# shed.net
KiCad netlist of a schematic drawn in EAGLE
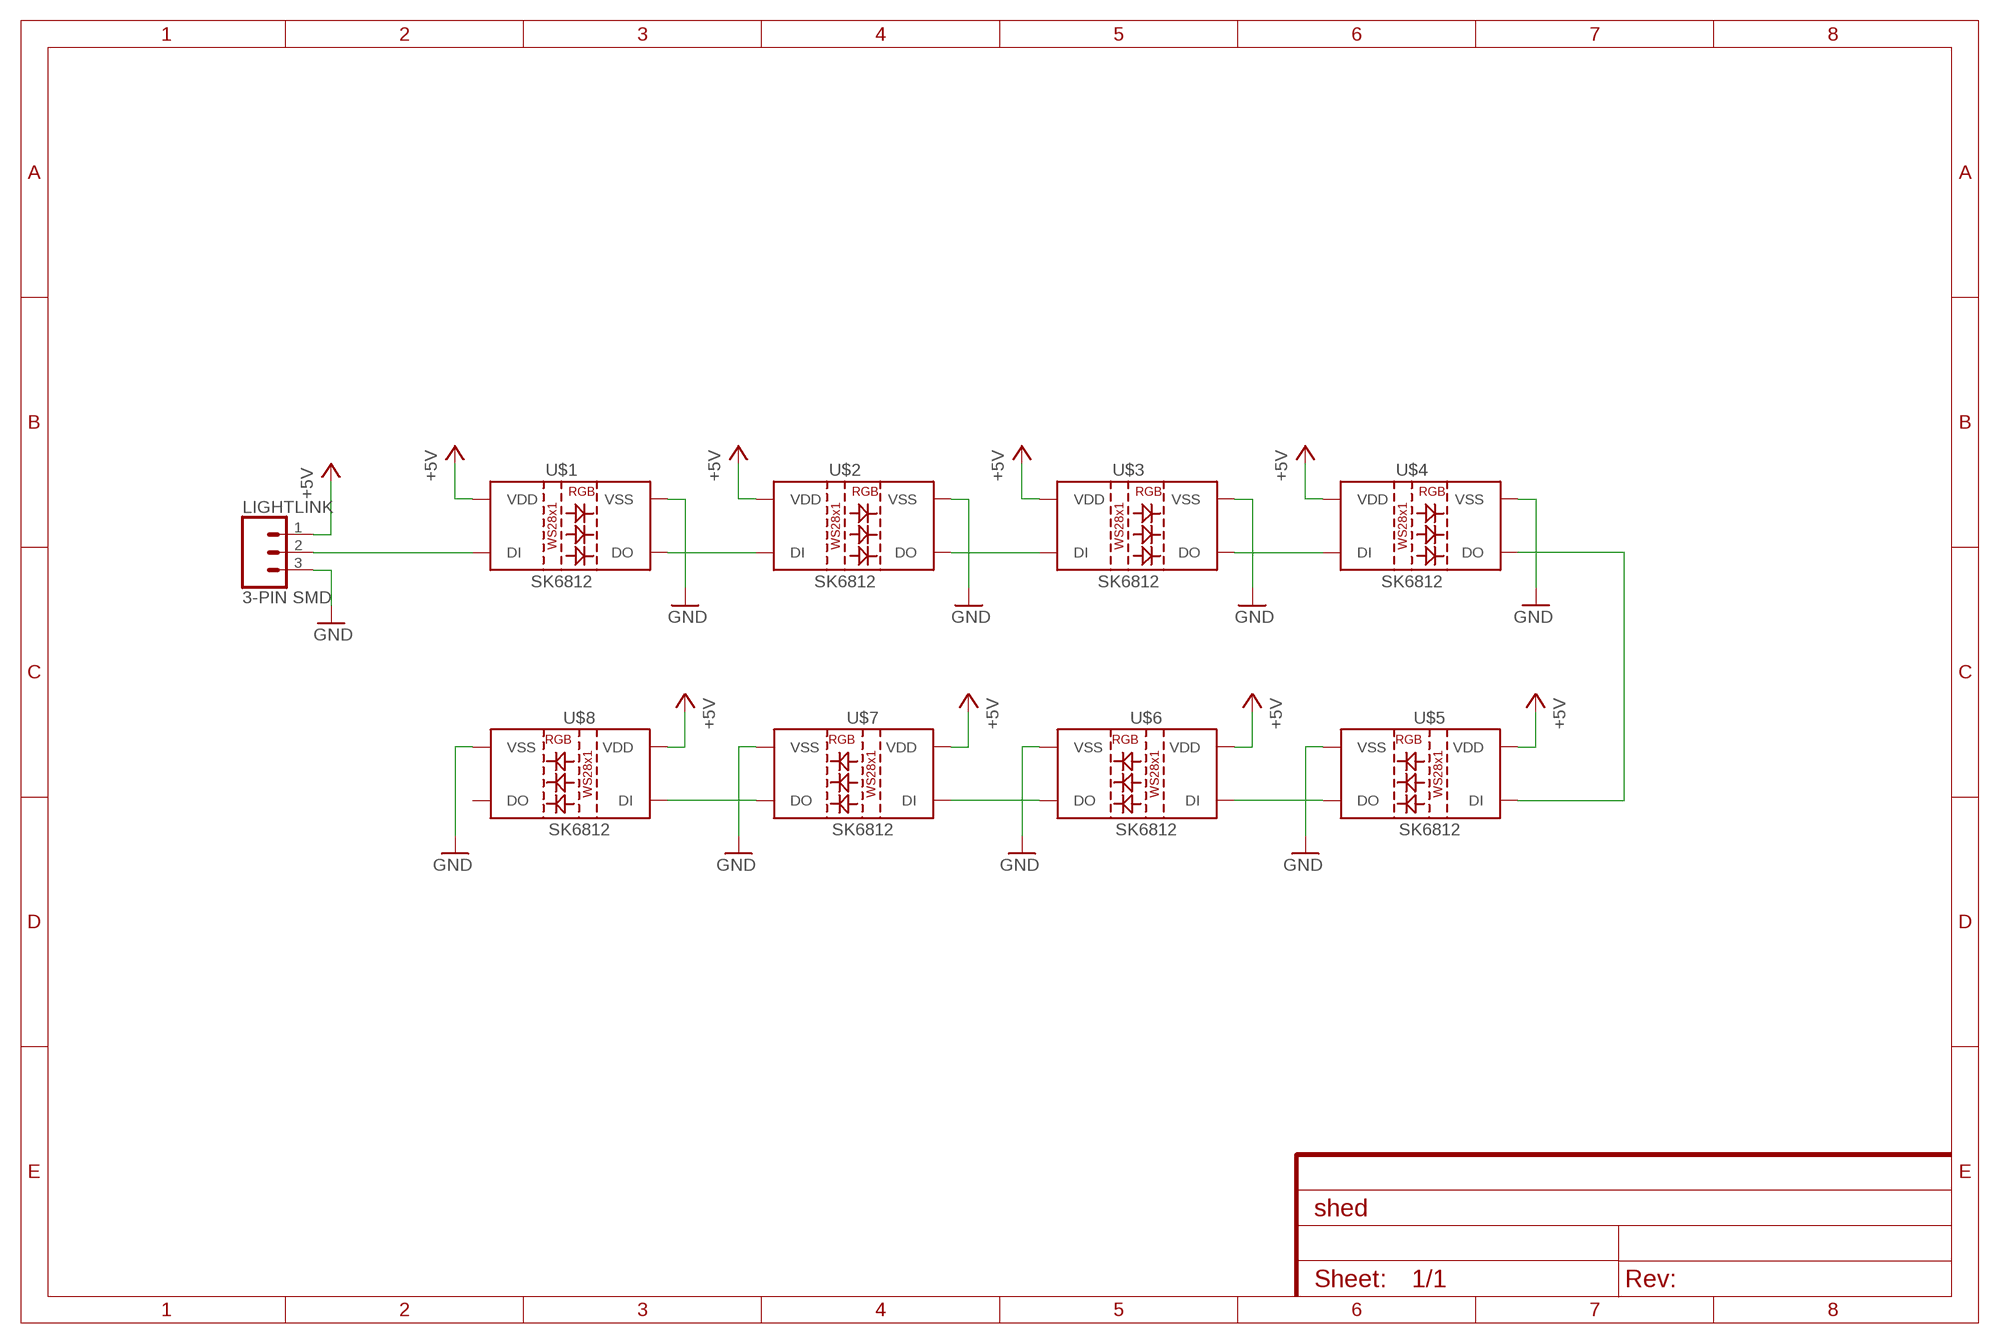
[diagram p0: schematic, sheet 1]

(export (version "E")
  (design (tool "Eeschema 10.0.6"))
  (components
    (comp (ref "LIGHTLINK")
      (value "3-PIN SMD")
      (footprint "eagle-import:JST-3-SMD")
      (libsource (lib "eagle-import") (part "CONN_03JST-SMD"))
    )
    (comp (ref "U$1")
      (value "SK6812")
      (footprint "eagle-import:LED3535")
      (libsource (lib "eagle-import") (part "SK6812"))
    )
    (comp (ref "U$2")
      (value "SK6812")
      (footprint "eagle-import:LED3535")
      (libsource (lib "eagle-import") (part "SK6812"))
    )
    (comp (ref "U$3")
      (value "SK6812")
      (footprint "eagle-import:LED3535")
      (libsource (lib "eagle-import") (part "SK6812"))
    )
    (comp (ref "U$4")
      (value "SK6812")
      (footprint "eagle-import:LED3535")
      (libsource (lib "eagle-import") (part "SK6812"))
    )
    (comp (ref "U$5")
      (value "SK6812")
      (footprint "eagle-import:LED3535")
      (libsource (lib "eagle-import") (part "SK6812"))
    )
    (comp (ref "U$6")
      (value "SK6812")
      (footprint "eagle-import:LED3535")
      (libsource (lib "eagle-import") (part "SK6812"))
    )
    (comp (ref "U$7")
      (value "SK6812")
      (footprint "eagle-import:LED3535")
      (libsource (lib "eagle-import") (part "SK6812"))
    )
    (comp (ref "U$8")
      (value "SK6812")
      (footprint "eagle-import:LED3535")
      (libsource (lib "eagle-import") (part "SK6812"))
    )
  )
  (nets
    (net (code "1") (name "+5V") (class "Default")
      (node (ref "LIGHTLINK") (pin "1") (pinfunction "3_1") (pintype "passive"))
      (node (ref "U$1") (pin "3") (pinfunction "VDD_3") (pintype "bidirectional"))
      (node (ref "U$2") (pin "3") (pinfunction "VDD_3") (pintype "bidirectional"))
      (node (ref "U$3") (pin "3") (pinfunction "VDD_3") (pintype "bidirectional"))
      (node (ref "U$4") (pin "3") (pinfunction "VDD_3") (pintype "bidirectional"))
      (node (ref "U$5") (pin "3") (pinfunction "VDD_3") (pintype "bidirectional"))
      (node (ref "U$6") (pin "3") (pinfunction "VDD_3") (pintype "bidirectional"))
      (node (ref "U$7") (pin "3") (pinfunction "VDD_3") (pintype "bidirectional"))
      (node (ref "U$8") (pin "3") (pinfunction "VDD_3") (pintype "bidirectional"))
    )
    (net (code "2") (name "GND") (class "Default")
      (node (ref "LIGHTLINK") (pin "3") (pinfunction "1_3") (pintype "passive"))
      (node (ref "U$1") (pin "1") (pinfunction "VSS_1") (pintype "bidirectional"))
      (node (ref "U$2") (pin "1") (pinfunction "VSS_1") (pintype "bidirectional"))
      (node (ref "U$3") (pin "1") (pinfunction "VSS_1") (pintype "bidirectional"))
      (node (ref "U$4") (pin "1") (pinfunction "VSS_1") (pintype "bidirectional"))
      (node (ref "U$5") (pin "1") (pinfunction "VSS_1") (pintype "bidirectional"))
      (node (ref "U$6") (pin "1") (pinfunction "VSS_1") (pintype "bidirectional"))
      (node (ref "U$7") (pin "1") (pinfunction "VSS_1") (pintype "bidirectional"))
      (node (ref "U$8") (pin "1") (pinfunction "VSS_1") (pintype "bidirectional"))
    )
    (net (code "3") (name "Net-(U$1-DI)") (class "Default")
      (node (ref "LIGHTLINK") (pin "2") (pinfunction "2_2") (pintype "passive"))
      (node (ref "U$1") (pin "2") (pinfunction "DI_2") (pintype "bidirectional"))
    )
    (net (code "4") (name "Net-(U$1-DO)") (class "Default")
      (node (ref "U$1") (pin "4") (pinfunction "DO_4") (pintype "bidirectional"))
      (node (ref "U$2") (pin "2") (pinfunction "DI_2") (pintype "bidirectional"))
    )
    (net (code "5") (name "Net-(U$2-DO)") (class "Default")
      (node (ref "U$2") (pin "4") (pinfunction "DO_4") (pintype "bidirectional"))
      (node (ref "U$3") (pin "2") (pinfunction "DI_2") (pintype "bidirectional"))
    )
    (net (code "6") (name "Net-(U$3-DO)") (class "Default")
      (node (ref "U$3") (pin "4") (pinfunction "DO_4") (pintype "bidirectional"))
      (node (ref "U$4") (pin "2") (pinfunction "DI_2") (pintype "bidirectional"))
    )
    (net (code "7") (name "Net-(U$4-DO)") (class "Default")
      (node (ref "U$4") (pin "4") (pinfunction "DO_4") (pintype "bidirectional"))
      (node (ref "U$5") (pin "2") (pinfunction "DI_2") (pintype "bidirectional"))
    )
    (net (code "8") (name "Net-(U$5-DO)") (class "Default")
      (node (ref "U$5") (pin "4") (pinfunction "DO_4") (pintype "bidirectional"))
      (node (ref "U$6") (pin "2") (pinfunction "DI_2") (pintype "bidirectional"))
    )
    (net (code "9") (name "Net-(U$6-DO)") (class "Default")
      (node (ref "U$6") (pin "4") (pinfunction "DO_4") (pintype "bidirectional"))
      (node (ref "U$7") (pin "2") (pinfunction "DI_2") (pintype "bidirectional"))
    )
    (net (code "10") (name "Net-(U$7-DO)") (class "Default")
      (node (ref "U$7") (pin "4") (pinfunction "DO_4") (pintype "bidirectional"))
      (node (ref "U$8") (pin "2") (pinfunction "DI_2") (pintype "bidirectional"))
    )
    (net (code "11") (name "unconnected-(U$8-DO-Pad4)") (class "Default")
      (node (ref "U$8") (pin "4") (pinfunction "DO_4") (pintype "bidirectional"))
    )
  )
)
